# Bedroom_Adapter.net
KiCad netlist of a schematic drawn in EAGLE
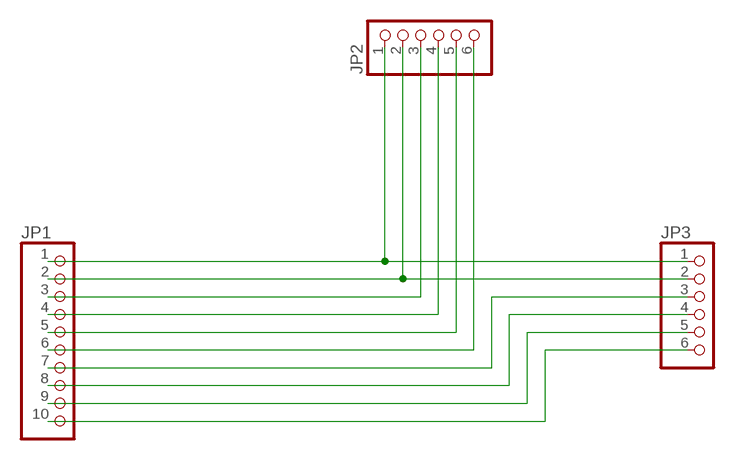
[diagram p0: schematic, sheet 1]

(export (version "E")
  (design (tool "Eeschema 10.0.6"))
  (components
    (comp (ref "JP1")
      (value "PINHD-1X10")
      (footprint "eagle-import:1X10")
      (libsource (lib "eagle-import") (part "PINHD-1X10"))
    )
    (comp (ref "JP2")
      (value "PINHD-1X6")
      (footprint "eagle-import:1X06")
      (libsource (lib "eagle-import") (part "PINHD-1X6"))
    )
    (comp (ref "JP3")
      (value "PINHD-1X6")
      (footprint "eagle-import:1X06")
      (libsource (lib "eagle-import") (part "PINHD-1X6"))
    )
  )
  (nets
    (net (code "1") (name "Net-(JP1-Pad1)") (class "Default")
      (node (ref "JP1") (pin "1") (pinfunction "1_1") (pintype "passive"))
      (node (ref "JP2") (pin "1") (pinfunction "1_1") (pintype "passive"))
      (node (ref "JP3") (pin "1") (pinfunction "1_1") (pintype "passive"))
    )
    (net (code "2") (name "Net-(JP1-Pad2)") (class "Default")
      (node (ref "JP1") (pin "2") (pinfunction "2_2") (pintype "passive"))
      (node (ref "JP2") (pin "2") (pinfunction "2_2") (pintype "passive"))
      (node (ref "JP3") (pin "2") (pinfunction "2_2") (pintype "passive"))
    )
    (net (code "3") (name "Net-(JP1-Pad3)") (class "Default")
      (node (ref "JP1") (pin "3") (pinfunction "3_3") (pintype "passive"))
      (node (ref "JP2") (pin "3") (pinfunction "3_3") (pintype "passive"))
    )
    (net (code "4") (name "Net-(JP1-Pad4)") (class "Default")
      (node (ref "JP1") (pin "4") (pinfunction "4_4") (pintype "passive"))
      (node (ref "JP2") (pin "4") (pinfunction "4_4") (pintype "passive"))
    )
    (net (code "5") (name "Net-(JP1-Pad5)") (class "Default")
      (node (ref "JP1") (pin "5") (pinfunction "5_5") (pintype "passive"))
      (node (ref "JP2") (pin "5") (pinfunction "5_5") (pintype "passive"))
    )
    (net (code "6") (name "Net-(JP1-Pad6)") (class "Default")
      (node (ref "JP1") (pin "6") (pinfunction "6_6") (pintype "passive"))
      (node (ref "JP2") (pin "6") (pinfunction "6_6") (pintype "passive"))
    )
    (net (code "7") (name "Net-(JP1-Pad7)") (class "Default")
      (node (ref "JP1") (pin "7") (pinfunction "7_7") (pintype "passive"))
      (node (ref "JP3") (pin "3") (pinfunction "3_3") (pintype "passive"))
    )
    (net (code "8") (name "Net-(JP1-Pad8)") (class "Default")
      (node (ref "JP1") (pin "8") (pinfunction "8_8") (pintype "passive"))
      (node (ref "JP3") (pin "4") (pinfunction "4_4") (pintype "passive"))
    )
    (net (code "9") (name "Net-(JP1-Pad9)") (class "Default")
      (node (ref "JP1") (pin "9") (pinfunction "9_9") (pintype "passive"))
      (node (ref "JP3") (pin "5") (pinfunction "5_5") (pintype "passive"))
    )
    (net (code "10") (name "Net-(JP1-Pad10)") (class "Default")
      (node (ref "JP1") (pin "10") (pinfunction "10_10") (pintype "passive"))
      (node (ref "JP3") (pin "6") (pinfunction "6_6") (pintype "passive"))
    )
  )
)
